# clk_shield.net
KiCad netlist of a schematic drawn in EAGLE
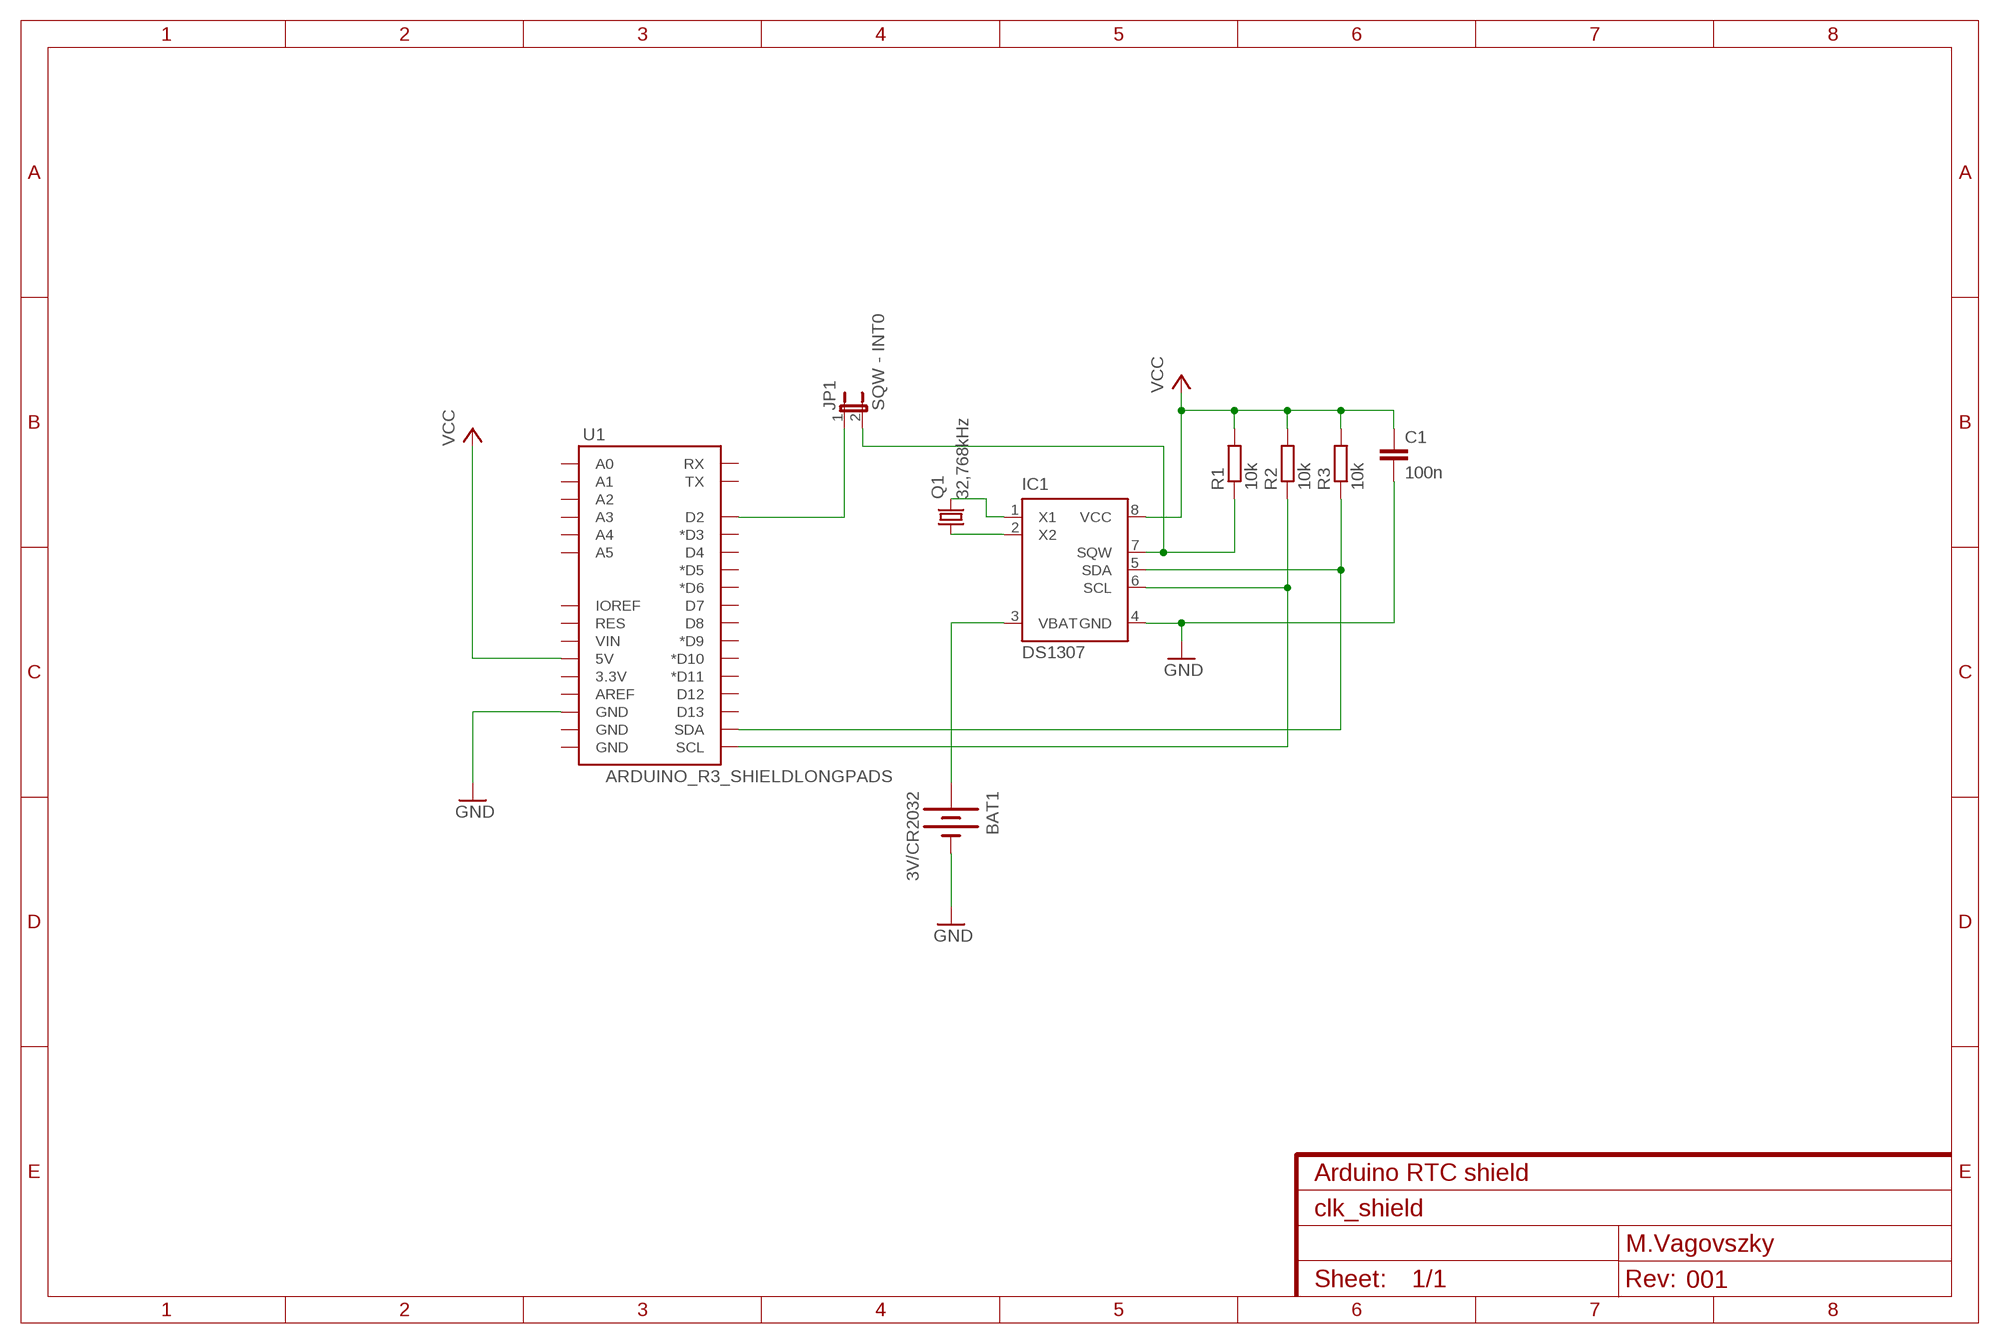
[diagram p0: schematic, sheet 1]

(export (version "E")
  (design (tool "Eeschema 10.0.6"))
  (components
    (comp (ref "BAT1")
      (value "3V/CR2032")
      (footprint "eagle-import:BATTCOM_20MM_PTH")
      (libsource (lib "eagle-import") (part "BATTERY20PTH"))
    )
    (comp (ref "C1")
      (value "100n")
      (footprint "eagle-import:C050-025X075")
      (libsource (lib "eagle-import") (part "C-EU050-025X075"))
    )
    (comp (ref "IC1")
      (value "DS1307")
      (footprint "eagle-import:DIP-8")
      (libsource (lib "eagle-import") (part "DS1307"))
    )
    (comp (ref "JP1")
      (value "SQW - INT0")
      (footprint "eagle-import:1X02")
      (libsource (lib "eagle-import") (part "JUMPER-2PTH"))
    )
    (comp (ref "Q1")
      (value "32,768kHz")
      (footprint "eagle-import:TC26H")
      (libsource (lib "eagle-import") (part "CRYSTALTC26H"))
    )
    (comp (ref "R1")
      (value "10k")
      (footprint "eagle-import:0207_12")
      (libsource (lib "eagle-import") (part "R-EU_0207/12"))
    )
    (comp (ref "R2")
      (value "10k")
      (footprint "eagle-import:0207_12")
      (libsource (lib "eagle-import") (part "R-EU_0207/12"))
    )
    (comp (ref "R3")
      (value "10k")
      (footprint "eagle-import:0207_12")
      (libsource (lib "eagle-import") (part "R-EU_0207/12"))
    )
    (comp (ref "U1")
      (value "ARDUINO_R3_SHIELDLONGPADS")
      (footprint "eagle-import:UNO_R3_SHIELD_LONGPADS")
      (libsource (lib "eagle-import") (part "ARDUINO_R3_SHIELDLONGPADS"))
    )
  )
  (nets
    (net (code "1") (name "GND") (class "Default")
      (node (ref "BAT1") (pin "2") (pinfunction "-_2") (pintype "power_in"))
      (node (ref "C1") (pin "2") (pinfunction "2_2") (pintype "passive"))
      (node (ref "IC1") (pin "4") (pinfunction "GND_4") (pintype "power_in"))
      (node (ref "U1") (pin "GND@2") (pinfunction "GND_GND@2") (pintype "bidirectional"))
    )
    (net (code "2") (name "Net-(BAT1-+)") (class "Default")
      (node (ref "BAT1") (pin "1") (pinfunction "+_1") (pintype "power_in"))
      (node (ref "IC1") (pin "3") (pinfunction "VBAT_3") (pintype "input"))
    )
    (net (code "3") (name "Net-(IC1-SCL)") (class "Default")
      (node (ref "IC1") (pin "6") (pinfunction "SCL_6") (pintype "input"))
      (node (ref "R2") (pin "1") (pinfunction "1_1") (pintype "passive"))
      (node (ref "U1") (pin "SCL") (pinfunction "SCL_SCL") (pintype "bidirectional"))
    )
    (net (code "4") (name "Net-(IC1-SDA)") (class "Default")
      (node (ref "IC1") (pin "5") (pinfunction "SDA_5") (pintype "output"))
      (node (ref "R3") (pin "1") (pinfunction "1_1") (pintype "passive"))
      (node (ref "U1") (pin "SDA") (pinfunction "SDA_SDA") (pintype "bidirectional"))
    )
    (net (code "5") (name "Net-(IC1-SQW)") (class "Default")
      (node (ref "IC1") (pin "7") (pinfunction "SQW_7") (pintype "input"))
      (node (ref "JP1") (pin "2") (pinfunction "2_2") (pintype "passive"))
      (node (ref "R1") (pin "1") (pinfunction "1_1") (pintype "passive"))
    )
    (net (code "6") (name "Net-(IC1-X1)") (class "Default")
      (node (ref "IC1") (pin "1") (pinfunction "X1_1") (pintype "input"))
      (node (ref "Q1") (pin "2") (pinfunction "2_2") (pintype "passive"))
    )
    (net (code "7") (name "Net-(IC1-X2)") (class "Default")
      (node (ref "IC1") (pin "2") (pinfunction "X2_2") (pintype "input"))
      (node (ref "Q1") (pin "1") (pinfunction "1_1") (pintype "passive"))
    )
    (net (code "8") (name "Net-(JP1-Pad1)") (class "Default")
      (node (ref "JP1") (pin "1") (pinfunction "1_1") (pintype "passive"))
      (node (ref "U1") (pin "D2") (pinfunction "D2_D2") (pintype "bidirectional"))
    )
    (net (code "9") (name "VCC") (class "Default")
      (node (ref "C1") (pin "1") (pinfunction "1_1") (pintype "passive"))
      (node (ref "IC1") (pin "8") (pinfunction "VCC_8") (pintype "power_in"))
      (node (ref "R1") (pin "2") (pinfunction "2_2") (pintype "passive"))
      (node (ref "R2") (pin "2") (pinfunction "2_2") (pintype "passive"))
      (node (ref "R3") (pin "2") (pinfunction "2_2") (pintype "passive"))
      (node (ref "U1") (pin "5V") (pinfunction "5V_5V") (pintype "bidirectional"))
    )
    (net (code "10") (name "unconnected-(U1-*D3-PadD3)") (class "Default")
      (node (ref "U1") (pin "D3") (pinfunction "*D3_D3") (pintype "bidirectional"))
    )
    (net (code "11") (name "unconnected-(U1-*D5-PadD5)") (class "Default")
      (node (ref "U1") (pin "D5") (pinfunction "*D5_D5") (pintype "bidirectional"))
    )
    (net (code "12") (name "unconnected-(U1-*D6-PadD6)") (class "Default")
      (node (ref "U1") (pin "D6") (pinfunction "*D6_D6") (pintype "bidirectional"))
    )
    (net (code "13") (name "unconnected-(U1-*D9-PadD9)") (class "Default")
      (node (ref "U1") (pin "D9") (pinfunction "*D9_D9") (pintype "bidirectional"))
    )
    (net (code "14") (name "unconnected-(U1-*D10-PadD10)") (class "Default")
      (node (ref "U1") (pin "D10") (pinfunction "*D10_D10") (pintype "bidirectional"))
    )
    (net (code "15") (name "unconnected-(U1-*D11-PadD11)") (class "Default")
      (node (ref "U1") (pin "D11") (pinfunction "*D11_D11") (pintype "bidirectional"))
    )
    (net (code "16") (name "unconnected-(U1-GND-PadGND@0)") (class "Default")
      (node (ref "U1") (pin "GND@0") (pinfunction "GND_GND@0") (pintype "bidirectional"))
    )
    (net (code "17") (name "unconnected-(U1-GND-PadGND@1)") (class "Default")
      (node (ref "U1") (pin "GND@1") (pinfunction "GND_GND@1") (pintype "bidirectional"))
    )
    (net (code "18") (name "unconnected-(U1-Pad3.3V)") (class "Default")
      (node (ref "U1") (pin "3.3V") (pinfunction "3.3V_3.3V") (pintype "bidirectional"))
    )
    (net (code "19") (name "unconnected-(U1-PadA0)") (class "Default")
      (node (ref "U1") (pin "A0") (pinfunction "A0_A0") (pintype "bidirectional"))
    )
    (net (code "20") (name "unconnected-(U1-PadA1)") (class "Default")
      (node (ref "U1") (pin "A1") (pinfunction "A1_A1") (pintype "bidirectional"))
    )
    (net (code "21") (name "unconnected-(U1-PadA2)") (class "Default")
      (node (ref "U1") (pin "A2") (pinfunction "A2_A2") (pintype "bidirectional"))
    )
    (net (code "22") (name "unconnected-(U1-PadA3)") (class "Default")
      (node (ref "U1") (pin "A3") (pinfunction "A3_A3") (pintype "bidirectional"))
    )
    (net (code "23") (name "unconnected-(U1-PadA4)") (class "Default")
      (node (ref "U1") (pin "A4") (pinfunction "A4_A4") (pintype "bidirectional"))
    )
    (net (code "24") (name "unconnected-(U1-PadA5)") (class "Default")
      (node (ref "U1") (pin "A5") (pinfunction "A5_A5") (pintype "bidirectional"))
    )
    (net (code "25") (name "unconnected-(U1-PadAREF)") (class "Default")
      (node (ref "U1") (pin "AREF") (pinfunction "AREF_AREF") (pintype "bidirectional"))
    )
    (net (code "26") (name "unconnected-(U1-PadD4)") (class "Default")
      (node (ref "U1") (pin "D4") (pinfunction "D4_D4") (pintype "bidirectional"))
    )
    (net (code "27") (name "unconnected-(U1-PadD7)") (class "Default")
      (node (ref "U1") (pin "D7") (pinfunction "D7_D7") (pintype "bidirectional"))
    )
    (net (code "28") (name "unconnected-(U1-PadD8)") (class "Default")
      (node (ref "U1") (pin "D8") (pinfunction "D8_D8") (pintype "bidirectional"))
    )
    (net (code "29") (name "unconnected-(U1-PadD12)") (class "Default")
      (node (ref "U1") (pin "D12") (pinfunction "D12_D12") (pintype "bidirectional"))
    )
    (net (code "30") (name "unconnected-(U1-PadD13)") (class "Default")
      (node (ref "U1") (pin "D13") (pinfunction "D13_D13") (pintype "bidirectional"))
    )
    (net (code "31") (name "unconnected-(U1-PadIOREF)") (class "Default")
      (node (ref "U1") (pin "IOREF") (pinfunction "IOREF_IOREF") (pintype "bidirectional"))
    )
    (net (code "32") (name "unconnected-(U1-PadRES)") (class "Default")
      (node (ref "U1") (pin "RES") (pinfunction "RES_RES") (pintype "bidirectional"))
    )
    (net (code "33") (name "unconnected-(U1-PadRX)") (class "Default")
      (node (ref "U1") (pin "RX") (pinfunction "RX_RX") (pintype "bidirectional"))
    )
    (net (code "34") (name "unconnected-(U1-PadTX)") (class "Default")
      (node (ref "U1") (pin "TX") (pinfunction "TX_TX") (pintype "bidirectional"))
    )
    (net (code "35") (name "unconnected-(U1-PadVIN)") (class "Default")
      (node (ref "U1") (pin "VIN") (pinfunction "VIN_VIN") (pintype "bidirectional"))
    )
  )
)
